# currgenTPA.net
KiCad netlist of a schematic drawn in Altium Designer
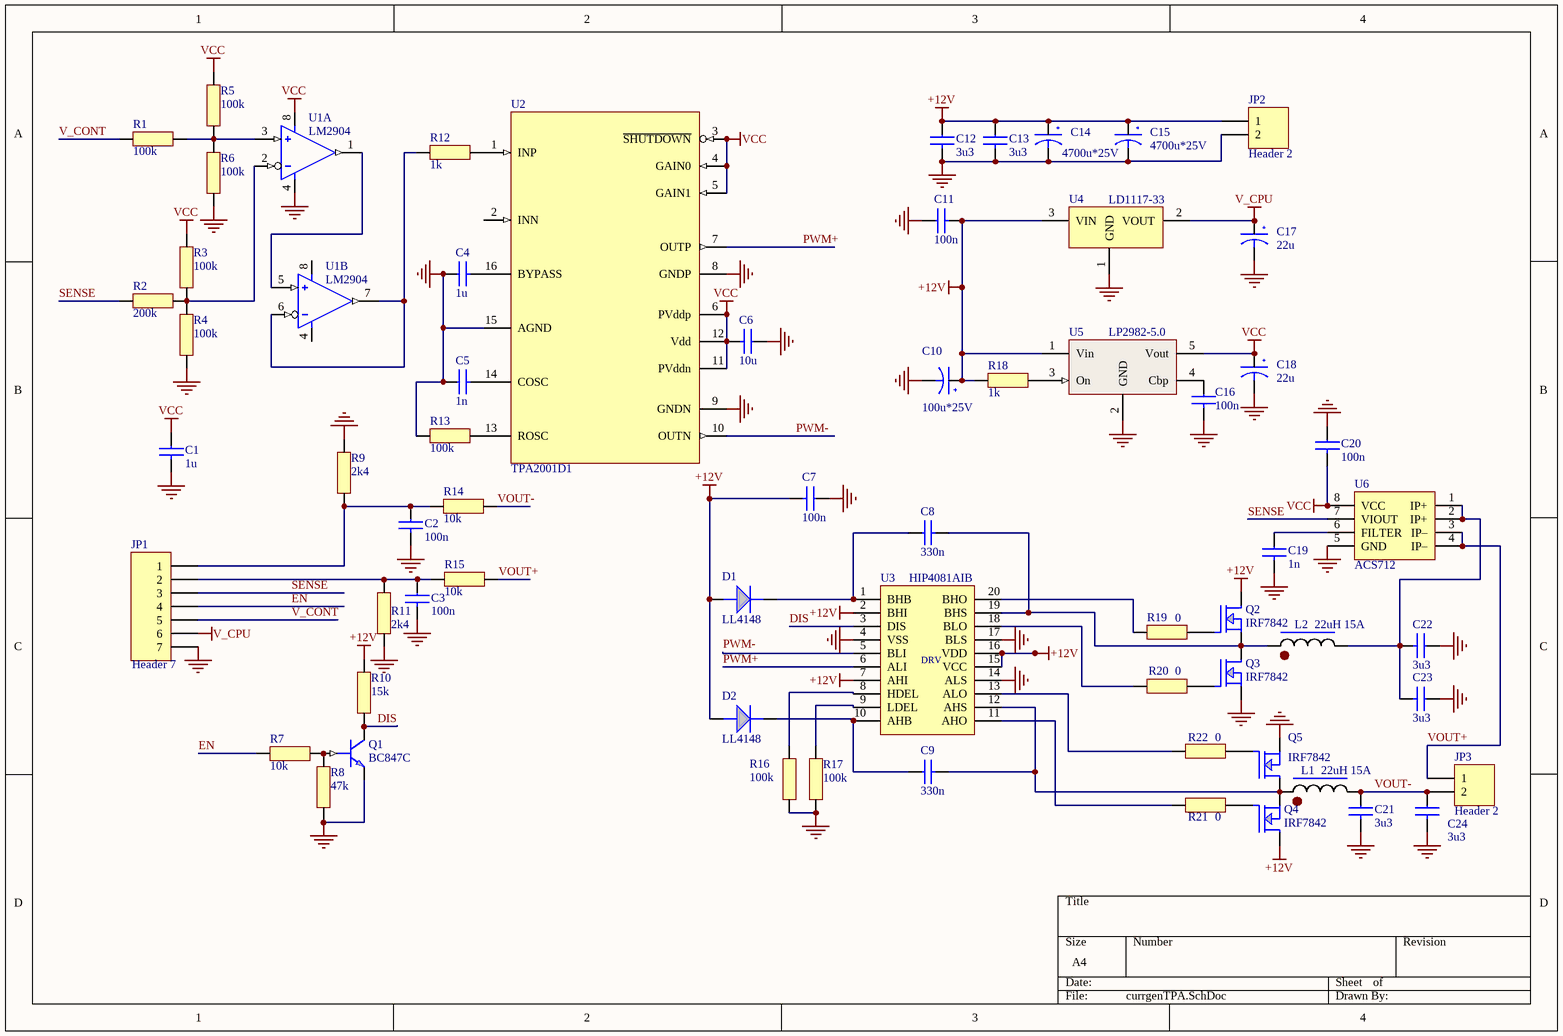
[diagram p0: currgenTPA.SchDoc]

(export (version "E")
  (design (tool "Eeschema 10.0.6"))
  (components
    (comp (ref "C1") (value "1u") (footprint "C-0805") (libsource (lib "RCS-Discret") (part "C")))
    (comp (ref "C2") (value "100n") (footprint "C-0805") (libsource (lib "RCS-Discret") (part "C")))
    (comp (ref "C3") (value "100n") (footprint "C-0805") (libsource (lib "RCS-Discret") (part "C")))
    (comp (ref "C4") (value "1u") (footprint "C-0805") (libsource (lib "RCS-Discret") (part "C")))
    (comp (ref "C5") (value "1n") (footprint "C-0805") (libsource (lib "RCS-Discret") (part "C")))
    (comp (ref "C6") (value "10u") (footprint "C-0805") (libsource (lib "RCS-Discret") (part "C")))
    (comp (ref "C7") (value "100n") (footprint "C-0805") (libsource (lib "RCS-Discret") (part "C")))
    (comp (ref "C8") (value "330n") (footprint "C-0805") (libsource (lib "RCS-Discret") (part "C")))
    (comp (ref "C9") (value "330n") (footprint "C-0805") (libsource (lib "RCS-Discret") (part "C")))
    (comp (ref "C10")
      (value "100u*25V")
      (footprint "EXR-6.3X11")
      (libsource (lib "RCS-Discret") (part "C-EL-DIP"))
    )
    (comp (ref "C11") (value "100n") (footprint "C-0805") (libsource (lib "RCS-Discret") (part "C")))
    (comp (ref "C12") (value "3u3") (footprint "C-1206") (libsource (lib "RCS-Discret") (part "C")))
    (comp (ref "C13") (value "3u3") (footprint "C-1206") (libsource (lib "RCS-Discret") (part "C")))
    (comp (ref "C14")
      (value "4700u*25V")
      (footprint "EXR-10X12.5")
      (libsource (lib "RCS-Discret") (part "C-EL-DIP"))
    )
    (comp (ref "C15")
      (value "4700u*25V")
      (footprint "EXR-10X12.5")
      (libsource (lib "RCS-Discret") (part "C-EL-DIP"))
    )
    (comp (ref "C16") (value "100n") (footprint "C-0805") (libsource (lib "RCS-Discret") (part "C")))
    (comp (ref "C17") (value "22u") (footprint "TANTAL-A") (libsource (lib "RCS-Discret") (part "C-EL-TAN")))
    (comp (ref "C18") (value "22u") (footprint "TANTAL-A") (libsource (lib "RCS-Discret") (part "C-EL-TAN")))
    (comp (ref "C19") (value "1n") (footprint "C-0805") (libsource (lib "RCS-Discret") (part "C")))
    (comp (ref "C20") (value "100n") (footprint "C-0805") (libsource (lib "RCS-Discret") (part "C")))
    (comp (ref "C21") (value "3u3") (footprint "C-1206") (libsource (lib "RCS-Discret") (part "C")))
    (comp (ref "C22") (value "3u3") (footprint "C-1206") (libsource (lib "RCS-Discret") (part "C")))
    (comp (ref "C23") (value "3u3") (footprint "C-1206") (libsource (lib "RCS-Discret") (part "C")))
    (comp (ref "C24") (value "3u3") (footprint "C-1206") (libsource (lib "RCS-Discret") (part "C")))
    (comp (ref "D1") (value "LL4148") (footprint "SOD-80") (libsource (lib "RCS-Discret") (part "DIODE")))
    (comp (ref "D2") (value "LL4148") (footprint "SOD-80") (libsource (lib "RCS-Discret") (part "DIODE")))
    (comp (ref "JP1")
      (value "Header 7")
      (footprint "HDR1X7")
      (description "Header, 7-Pin")
      (fields (field (name "PUBLISHER") "Altium Limited"))
      (libsource (lib "Miscellaneous Connectors") (part "Header 7"))
    )
    (comp (ref "JP2")
      (value "Header 2")
      (footprint "KLEMMA2")
      (description "Header, 2-Pin")
      (fields (field (name "PUBLISHER") "Altium Limited"))
      (libsource (lib "Miscellaneous Connectors") (part "Header 2"))
    )
    (comp (ref "JP3")
      (value "Header 2")
      (footprint "KLEMMA2")
      (description "Header, 2-Pin")
      (fields (field (name "PUBLISHER") "Altium Limited"))
      (libsource (lib "Miscellaneous Connectors") (part "Header 2"))
    )
    (comp (ref "L1") (value "22uH 15A") (footprint "L_TOR") (libsource (lib "RCS-Discret") (part "L*")))
    (comp (ref "L2") (value "22uH 15A") (footprint "L_TOR") (libsource (lib "RCS-Discret") (part "L*")))
    (comp (ref "Q1") (value "BC847C") (footprint "SOT-23") (libsource (lib "RCS-Discret") (part "NPN")))
    (comp (ref "Q2") (value "IRF7842") (footprint "SO8_MOSFET") (libsource (lib "currgen") (part "IRF7842")))
    (comp (ref "Q3") (value "IRF7842") (footprint "SO8_MOSFET") (libsource (lib "currgen") (part "IRF7842")))
    (comp (ref "Q4") (value "IRF7842") (footprint "SO8_MOSFET") (libsource (lib "currgen") (part "IRF7842")))
    (comp (ref "Q5") (value "IRF7842") (footprint "SO8_MOSFET") (libsource (lib "currgen") (part "IRF7842")))
    (comp (ref "R1") (value "100k") (footprint "R-0805") (libsource (lib "") (part "R_1")))
    (comp (ref "R2") (value "200k") (footprint "R-0805") (libsource (lib "") (part "R_1")))
    (comp (ref "R3") (value "100k") (footprint "R-0805") (libsource (lib "RCS-Discret") (part "R")))
    (comp (ref "R4") (value "100k") (footprint "R-0805") (libsource (lib "RCS-Discret") (part "R")))
    (comp (ref "R5") (value "100k") (footprint "R-0805") (libsource (lib "RCS-Discret") (part "R")))
    (comp (ref "R6") (value "100k") (footprint "R-0805") (libsource (lib "RCS-Discret") (part "R")))
    (comp (ref "R7") (value "10k") (footprint "R-0805") (libsource (lib "") (part "R_1")))
    (comp (ref "R8") (value "47k") (footprint "R-0805") (libsource (lib "RCS-Discret") (part "R")))
    (comp (ref "R9") (value "2k4") (footprint "R-0805") (libsource (lib "RCS-Discret") (part "R")))
    (comp (ref "R10") (value "15k") (footprint "R-0805") (libsource (lib "RCS-Discret") (part "R")))
    (comp (ref "R11") (value "2k4") (footprint "R-0805") (libsource (lib "RCS-Discret") (part "R")))
    (comp (ref "R12") (value "1k") (footprint "R-0805") (libsource (lib "") (part "R_1")))
    (comp (ref "R13") (value "100k") (footprint "R-0805") (libsource (lib "") (part "R_2")))
    (comp (ref "R14") (value "10k") (footprint "R-0805") (libsource (lib "") (part "R_1")))
    (comp (ref "R15") (value "10k") (footprint "R-0805") (libsource (lib "") (part "R_1")))
    (comp (ref "R16") (value "100k") (footprint "R-0805") (libsource (lib "") (part "R_3")))
    (comp (ref "R17") (value "100k") (footprint "R-0805") (libsource (lib "") (part "R_3")))
    (comp (ref "R18") (value "1k") (footprint "R-0805") (libsource (lib "") (part "R_1")))
    (comp (ref "R19") (value "0") (footprint "R-0805") (libsource (lib "") (part "R_1")))
    (comp (ref "R20") (value "0") (footprint "R-0805") (libsource (lib "") (part "R_1")))
    (comp (ref "R21") (value "0") (footprint "R-0805") (libsource (lib "") (part "R_1")))
    (comp (ref "R22") (value "0") (footprint "R-0805") (libsource (lib "") (part "R_1")))
    (comp (ref "U1")
      (value "LM2904")
      (footprint "SO8-(SOT-96-1)")
      (description "2 Operation amplifier")
      (libsource (lib "RCS-IMS") (part "LM2904"))
    )
    (comp (ref "U2")
      (value "TPA2001D1")
      (footprint "TSSOP16-(SOT-403-1)")
      (description "1-W FILTERLESS MONO AUDIO POWER AMPLIFIER")
      (libsource (lib "RCS-IMS") (part "TPA2001D1"))
    )
    (comp (ref "U3")
      (value "HIP4081AIB")
      (footprint "SO20-(SOT-163-1)")
      (libsource (lib "RCS-IMS") (part "HIP4081AIB"))
    )
    (comp (ref "U4")
      (value "LD1117-33")
      (footprint "SOT-223-(SC-73)")
      (libsource (lib "RCS-IMS") (part "LD1117"))
    )
    (comp (ref "U5")
      (value "LP2982-5.0")
      (footprint "SOT-23-5")
      (description "50mA Ultra Low-Dropout Regulator")
      (libsource (lib "RCS-IMS") (part "LP2982"))
    )
    (comp (ref "U6")
      (value "ACS712")
      (footprint "SO8-(SOT-96-1)")
      (libsource (lib "RCS-IMS") (part "ACS712"))
    )
  )
  (nets
    (net (code "1") (name "+12V") (class "Default")
      (node (ref "C10") (pin "2") (pinfunction "+_2") (pintype "passive"))
      (node (ref "C11") (pin "2") (pinfunction "2_2") (pintype "passive"))
      (node (ref "C12") (pin "1") (pinfunction "1_1") (pintype "passive"))
      (node (ref "C13") (pin "1") (pinfunction "1_1") (pintype "passive"))
      (node (ref "C14") (pin "2") (pinfunction "+_2") (pintype "passive"))
      (node (ref "C15") (pin "2") (pinfunction "+_2") (pintype "passive"))
      (node (ref "C7") (pin "2") (pinfunction "2_2") (pintype "passive"))
      (node (ref "D1") (pin "A") (pinfunction "A_A") (pintype "passive"))
      (node (ref "D2") (pin "A") (pinfunction "A_A") (pintype "passive"))
      (node (ref "JP2") (pin "1") (pinfunction "1_1") (pintype "passive"))
      (node (ref "Q2") (pin "5") (pinfunction "DRAIN_5") (pintype "passive"))
      (node (ref "Q4") (pin "5") (pinfunction "DRAIN_5") (pintype "passive"))
      (node (ref "R10") (pin "1") (pinfunction "1_1") (pintype "passive"))
      (node (ref "R18") (pin "1") (pinfunction "1_1") (pintype "passive"))
      (node (ref "U3") (pin "15") (pinfunction "VCC_15") (pintype "passive"))
      (node (ref "U3") (pin "16") (pinfunction "VDD_16") (pintype "passive"))
      (node (ref "U3") (pin "2") (pinfunction "BHI_2") (pintype "passive"))
      (node (ref "U3") (pin "7") (pinfunction "AHI_7") (pintype "passive"))
      (node (ref "U4") (pin "3") (pinfunction "VIN_3") (pintype "passive"))
      (node (ref "U5") (pin "1") (pinfunction "Vin_1") (pintype "power_in"))
    )
    (net (code "2") (name "/DIS") (class "Default")
      (node (ref "Q1") (pin "3") (pinfunction "COLLECTOR_3") (pintype "passive"))
      (node (ref "R10") (pin "2") (pinfunction "2_2") (pintype "passive"))
      (node (ref "U3") (pin "3") (pinfunction "DIS_3") (pintype "passive"))
    )
    (net (code "3") (name "/EN") (class "Default")
      (node (ref "JP1") (pin "4") (pinfunction "4_4") (pintype "passive"))
      (node (ref "R7") (pin "1") (pinfunction "1_1") (pintype "passive"))
    )
    (net (code "4") (name "/PWM+") (class "Default")
      (node (ref "U2") (pin "7") (pinfunction "OUTP_7") (pintype "output"))
      (node (ref "U3") (pin "6") (pinfunction "ALI_6") (pintype "passive"))
    )
    (net (code "5") (name "/PWM-") (class "Default")
      (node (ref "U2") (pin "10") (pinfunction "OUTN_10") (pintype "output"))
      (node (ref "U3") (pin "5") (pinfunction "BLI_5") (pintype "passive"))
    )
    (net (code "6") (name "/SENSE") (class "Default")
      (node (ref "JP1") (pin "3") (pinfunction "3_3") (pintype "passive"))
      (node (ref "R2") (pin "1") (pinfunction "1_1") (pintype "passive"))
      (node (ref "U6") (pin "7") (pinfunction "VIOUT_7") (pintype "passive"))
    )
    (net (code "7") (name "/VOUT+") (class "Default")
      (node (ref "JP3") (pin "1") (pinfunction "1_1") (pintype "passive"))
      (node (ref "R15") (pin "2") (pinfunction "2_2") (pintype "passive"))
      (node (ref "U6") (pin "3") (pinfunction "IP–_3") (pintype "passive"))
      (node (ref "U6") (pin "4") (pinfunction "IP–_4") (pintype "passive"))
    )
    (net (code "8") (name "/VOUT-") (class "Default")
      (node (ref "C21") (pin "1") (pinfunction "1_1") (pintype "passive"))
      (node (ref "C24") (pin "1") (pinfunction "1_1") (pintype "passive"))
      (node (ref "JP3") (pin "2") (pinfunction "2_2") (pintype "passive"))
      (node (ref "L1") (pin "2") (pinfunction "2_2") (pintype "passive"))
      (node (ref "R14") (pin "2") (pinfunction "2_2") (pintype "passive"))
    )
    (net (code "9") (name "/V_CONT") (class "Default")
      (node (ref "JP1") (pin "5") (pinfunction "5_5") (pintype "passive"))
      (node (ref "R1") (pin "1") (pinfunction "1_1") (pintype "passive"))
    )
    (net (code "10") (name "2") (class "Default")
      (node (ref "U4") (pin "4") (pinfunction "VOUT_4") (pintype "passive"))
    )
    (net (code "11") (name "GND") (class "Default")
      (node (ref "C1") (pin "2") (pinfunction "2_2") (pintype "passive"))
      (node (ref "C10") (pin "1") (pinfunction "-_1") (pintype "passive"))
      (node (ref "C11") (pin "1") (pinfunction "1_1") (pintype "passive"))
      (node (ref "C12") (pin "2") (pinfunction "2_2") (pintype "passive"))
      (node (ref "C13") (pin "2") (pinfunction "2_2") (pintype "passive"))
      (node (ref "C14") (pin "1") (pinfunction "-_1") (pintype "passive"))
      (node (ref "C15") (pin "1") (pinfunction "-_1") (pintype "passive"))
      (node (ref "C16") (pin "2") (pinfunction "2_2") (pintype "passive"))
      (node (ref "C17") (pin "1") (pinfunction "-_1") (pintype "passive"))
      (node (ref "C18") (pin "1") (pinfunction "-_1") (pintype "passive"))
      (node (ref "C19") (pin "2") (pinfunction "2_2") (pintype "passive"))
      (node (ref "C2") (pin "2") (pinfunction "2_2") (pintype "passive"))
      (node (ref "C20") (pin "1") (pinfunction "1_1") (pintype "passive"))
      (node (ref "C21") (pin "2") (pinfunction "2_2") (pintype "passive"))
      (node (ref "C22") (pin "1") (pinfunction "1_1") (pintype "passive"))
      (node (ref "C23") (pin "1") (pinfunction "1_1") (pintype "passive"))
      (node (ref "C24") (pin "2") (pinfunction "2_2") (pintype "passive"))
      (node (ref "C3") (pin "2") (pinfunction "2_2") (pintype "passive"))
      (node (ref "C4") (pin "1") (pinfunction "1_1") (pintype "passive"))
      (node (ref "C5") (pin "1") (pinfunction "1_1") (pintype "passive"))
      (node (ref "C6") (pin "1") (pinfunction "1_1") (pintype "passive"))
      (node (ref "C7") (pin "1") (pinfunction "1_1") (pintype "passive"))
      (node (ref "JP1") (pin "7") (pinfunction "7_7") (pintype "passive"))
      (node (ref "JP2") (pin "2") (pinfunction "2_2") (pintype "passive"))
      (node (ref "Q1") (pin "1") (pinfunction "EMITTER_1") (pintype "passive"))
      (node (ref "Q3") (pin "1") (pinfunction "SOURCE_1") (pintype "passive"))
      (node (ref "Q5") (pin "1") (pinfunction "SOURCE_1") (pintype "passive"))
      (node (ref "R11") (pin "2") (pinfunction "2_2") (pintype "passive"))
      (node (ref "R13") (pin "2") (pinfunction "2_2") (pintype "passive"))
      (node (ref "R16") (pin "1") (pinfunction "1_1") (pintype "passive"))
      (node (ref "R17") (pin "1") (pinfunction "1_1") (pintype "passive"))
      (node (ref "R4") (pin "2") (pinfunction "2_2") (pintype "passive"))
      (node (ref "R6") (pin "2") (pinfunction "2_2") (pintype "passive"))
      (node (ref "R8") (pin "2") (pinfunction "2_2") (pintype "passive"))
      (node (ref "R9") (pin "1") (pinfunction "1_1") (pintype "passive"))
      (node (ref "U1") (pin "4") (pinfunction "V-_4") (pintype "power_in"))
      (node (ref "U2") (pin "15") (pinfunction "AGND_15") (pintype "passive"))
      (node (ref "U2") (pin "8") (pinfunction "GNDP_8") (pintype "power_in"))
      (node (ref "U2") (pin "9") (pinfunction "GNDN_9") (pintype "power_in"))
      (node (ref "U3") (pin "14") (pinfunction "ALS_14") (pintype "passive"))
      (node (ref "U3") (pin "17") (pinfunction "BLS_17") (pintype "passive"))
      (node (ref "U3") (pin "4") (pinfunction "VSS_4") (pintype "passive"))
      (node (ref "U4") (pin "1") (pinfunction "GND_1") (pintype "passive"))
      (node (ref "U5") (pin "2") (pinfunction "GND_2") (pintype "power_in"))
      (node (ref "U6") (pin "5") (pinfunction "GND_5") (pintype "passive"))
    )
    (net (code "12") (name "Net-(C2-Pad1)") (class "Default")
      (node (ref "C2") (pin "1") (pinfunction "1_1") (pintype "passive"))
      (node (ref "JP1") (pin "1") (pinfunction "1_1") (pintype "passive"))
      (node (ref "R14") (pin "1") (pinfunction "1_1") (pintype "passive"))
      (node (ref "R9") (pin "2") (pinfunction "2_2") (pintype "passive"))
    )
    (net (code "13") (name "Net-(C3-Pad1)") (class "Default")
      (node (ref "C3") (pin "1") (pinfunction "1_1") (pintype "passive"))
      (node (ref "JP1") (pin "2") (pinfunction "2_2") (pintype "passive"))
      (node (ref "R11") (pin "1") (pinfunction "1_1") (pintype "passive"))
      (node (ref "R15") (pin "1") (pinfunction "1_1") (pintype "passive"))
    )
    (net (code "14") (name "Net-(C22-Pad2)") (class "Default")
      (node (ref "C22") (pin "2") (pinfunction "2_2") (pintype "passive"))
      (node (ref "C23") (pin "2") (pinfunction "2_2") (pintype "passive"))
      (node (ref "L2") (pin "2") (pinfunction "2_2") (pintype "passive"))
      (node (ref "U6") (pin "1") (pinfunction "IP+_1") (pintype "passive"))
      (node (ref "U6") (pin "2") (pinfunction "IP+_2") (pintype "passive"))
    )
    (net (code "15") (name "Net-(Q1-BASE)") (class "Default")
      (node (ref "Q1") (pin "2") (pinfunction "BASE_2") (pintype "input"))
      (node (ref "R7") (pin "2") (pinfunction "2_2") (pintype "passive"))
      (node (ref "R8") (pin "1") (pinfunction "1_1") (pintype "passive"))
    )
    (net (code "16") (name "Net-(Q2-GATE)") (class "Default")
      (node (ref "Q2") (pin "4") (pinfunction "GATE_4") (pintype "passive"))
      (node (ref "R19") (pin "2") (pinfunction "2_2") (pintype "passive"))
    )
    (net (code "17") (name "Net-(Q2-SOURCE)") (class "Default")
      (node (ref "C8") (pin "2") (pinfunction "2_2") (pintype "passive"))
      (node (ref "L2") (pin "1") (pinfunction "1_1") (pintype "passive"))
      (node (ref "Q2") (pin "1") (pinfunction "SOURCE_1") (pintype "passive"))
      (node (ref "Q3") (pin "5") (pinfunction "DRAIN_5") (pintype "passive"))
      (node (ref "U3") (pin "19") (pinfunction "BHS_19") (pintype "passive"))
    )
    (net (code "18") (name "Net-(Q3-GATE)") (class "Default")
      (node (ref "Q3") (pin "4") (pinfunction "GATE_4") (pintype "passive"))
      (node (ref "R20") (pin "2") (pinfunction "2_2") (pintype "passive"))
    )
    (net (code "19") (name "Net-(Q4-GATE)") (class "Default")
      (node (ref "Q4") (pin "4") (pinfunction "GATE_4") (pintype "passive"))
      (node (ref "R21") (pin "2") (pinfunction "2_2") (pintype "passive"))
    )
    (net (code "20") (name "Net-(Q4-SOURCE)") (class "Default")
      (node (ref "C9") (pin "2") (pinfunction "2_2") (pintype "passive"))
      (node (ref "L1") (pin "1") (pinfunction "1_1") (pintype "passive"))
      (node (ref "Q4") (pin "1") (pinfunction "SOURCE_1") (pintype "passive"))
      (node (ref "Q5") (pin "5") (pinfunction "DRAIN_5") (pintype "passive"))
      (node (ref "U3") (pin "12") (pinfunction "AHS_12") (pintype "passive"))
    )
    (net (code "21") (name "Net-(Q5-GATE)") (class "Default")
      (node (ref "Q5") (pin "4") (pinfunction "GATE_4") (pintype "passive"))
      (node (ref "R22") (pin "2") (pinfunction "2_2") (pintype "passive"))
    )
    (net (code "22") (name "Net-(U1A-+IN)") (class "Default")
      (node (ref "R1") (pin "2") (pinfunction "2_2") (pintype "passive"))
      (node (ref "R5") (pin "2") (pinfunction "2_2") (pintype "passive"))
      (node (ref "R6") (pin "1") (pinfunction "1_1") (pintype "passive"))
      (node (ref "U1") (pin "3") (pinfunction "+IN_3") (pintype "input"))
    )
    (net (code "23") (name "Net-(U1A--IN)") (class "Default")
      (node (ref "R2") (pin "2") (pinfunction "2_2") (pintype "passive"))
      (node (ref "R3") (pin "2") (pinfunction "2_2") (pintype "passive"))
      (node (ref "R4") (pin "1") (pinfunction "1_1") (pintype "passive"))
      (node (ref "U1") (pin "2") (pinfunction "-IN_2") (pintype "input"))
    )
    (net (code "24") (name "Net-(U1A-OUT)") (class "Default")
      (node (ref "U1") (pin "1") (pinfunction "OUT_1") (pintype "output"))
      (node (ref "U1") (pin "5") (pinfunction "+IN_5") (pintype "input"))
    )
    (net (code "25") (name "Net-(U1B--IN)") (class "Default")
      (node (ref "R12") (pin "1") (pinfunction "1_1") (pintype "passive"))
      (node (ref "U1") (pin "6") (pinfunction "-IN_6") (pintype "input"))
      (node (ref "U1") (pin "7") (pinfunction "OUT_7") (pintype "output"))
    )
    (net (code "26") (name "Net-(U2-BYPASS)") (class "Default")
      (node (ref "C4") (pin "2") (pinfunction "2_2") (pintype "passive"))
      (node (ref "U2") (pin "16") (pinfunction "BYPASS_16") (pintype "passive"))
    )
    (net (code "27") (name "Net-(U2-COSC)") (class "Default")
      (node (ref "C5") (pin "2") (pinfunction "2_2") (pintype "passive"))
      (node (ref "U2") (pin "14") (pinfunction "COSC_14") (pintype "passive"))
    )
    (net (code "28") (name "Net-(U2-INP)") (class "Default")
      (node (ref "R12") (pin "2") (pinfunction "2_2") (pintype "passive"))
      (node (ref "U2") (pin "1") (pinfunction "INP_1") (pintype "input"))
    )
    (net (code "29") (name "Net-(U2-ROSC)") (class "Default")
      (node (ref "R13") (pin "1") (pinfunction "1_1") (pintype "passive"))
      (node (ref "U2") (pin "13") (pinfunction "ROSC_13") (pintype "passive"))
    )
    (net (code "30") (name "Net-(U3-AHB)") (class "Default")
      (node (ref "C9") (pin "1") (pinfunction "1_1") (pintype "passive"))
      (node (ref "D2") (pin "K") (pinfunction "K_K") (pintype "passive"))
      (node (ref "U3") (pin "10") (pinfunction "AHB_10") (pintype "passive"))
    )
    (net (code "31") (name "Net-(U3-AHO)") (class "Default")
      (node (ref "R21") (pin "1") (pinfunction "1_1") (pintype "passive"))
      (node (ref "U3") (pin "11") (pinfunction "AHO_11") (pintype "passive"))
    )
    (net (code "32") (name "Net-(U3-ALO)") (class "Default")
      (node (ref "R22") (pin "1") (pinfunction "1_1") (pintype "passive"))
      (node (ref "U3") (pin "13") (pinfunction "ALO_13") (pintype "passive"))
    )
    (net (code "33") (name "Net-(U3-BHB)") (class "Default")
      (node (ref "C8") (pin "1") (pinfunction "1_1") (pintype "passive"))
      (node (ref "D1") (pin "K") (pinfunction "K_K") (pintype "passive"))
      (node (ref "U3") (pin "1") (pinfunction "BHB_1") (pintype "passive"))
    )
    (net (code "34") (name "Net-(U3-BHO)") (class "Default")
      (node (ref "R19") (pin "1") (pinfunction "1_1") (pintype "passive"))
      (node (ref "U3") (pin "20") (pinfunction "BHO_20") (pintype "passive"))
    )
    (net (code "35") (name "Net-(U3-BLO)") (class "Default")
      (node (ref "R20") (pin "1") (pinfunction "1_1") (pintype "passive"))
      (node (ref "U3") (pin "18") (pinfunction "BLO_18") (pintype "passive"))
    )
    (net (code "36") (name "Net-(U3-HDEL)") (class "Default")
      (node (ref "R16") (pin "2") (pinfunction "2_2") (pintype "passive"))
      (node (ref "U3") (pin "8") (pinfunction "HDEL_8") (pintype "passive"))
    )
    (net (code "37") (name "Net-(U3-LDEL)") (class "Default")
      (node (ref "R17") (pin "2") (pinfunction "2_2") (pintype "passive"))
      (node (ref "U3") (pin "9") (pinfunction "LDEL_9") (pintype "passive"))
    )
    (net (code "38") (name "Net-(U5-Cbp)") (class "Default")
      (node (ref "C16") (pin "1") (pinfunction "1_1") (pintype "passive"))
      (node (ref "U5") (pin "4") (pinfunction "Cbp_4") (pintype "passive"))
    )
    (net (code "39") (name "Net-(U5-On)") (class "Default")
      (node (ref "R18") (pin "2") (pinfunction "2_2") (pintype "passive"))
      (node (ref "U5") (pin "3") (pinfunction "On_3") (pintype "input"))
    )
    (net (code "40") (name "Net-(U6-FILTER)") (class "Default")
      (node (ref "C19") (pin "1") (pinfunction "1_1") (pintype "passive"))
      (node (ref "U6") (pin "6") (pinfunction "FILTER_6") (pintype "passive"))
    )
    (net (code "41") (name "VCC") (class "Default")
      (node (ref "C1") (pin "1") (pinfunction "1_1") (pintype "passive"))
      (node (ref "C18") (pin "2") (pinfunction "+_2") (pintype "passive"))
      (node (ref "C20") (pin "2") (pinfunction "2_2") (pintype "passive"))
      (node (ref "C6") (pin "2") (pinfunction "2_2") (pintype "passive"))
      (node (ref "R3") (pin "1") (pinfunction "1_1") (pintype "passive"))
      (node (ref "R5") (pin "1") (pinfunction "1_1") (pintype "passive"))
      (node (ref "U1") (pin "8") (pinfunction "V+_8") (pintype "power_in"))
      (node (ref "U2") (pin "11") (pinfunction "PVddn_11") (pintype "passive"))
      (node (ref "U2") (pin "12") (pinfunction "Vdd_12") (pintype "passive"))
      (node (ref "U2") (pin "3") (pinfunction "~{SHUTDOWN}_3") (pintype "input"))
      (node (ref "U2") (pin "4") (pinfunction "GAIN0_4") (pintype "input"))
      (node (ref "U2") (pin "5") (pinfunction "GAIN1_5") (pintype "input"))
      (node (ref "U2") (pin "6") (pinfunction "PVddp_6") (pintype "passive"))
      (node (ref "U5") (pin "5") (pinfunction "Vout_5") (pintype "power_in"))
      (node (ref "U6") (pin "8") (pinfunction "VCC_8") (pintype "passive"))
    )
    (net (code "42") (name "V_CPU") (class "Default")
      (node (ref "C17") (pin "2") (pinfunction "+_2") (pintype "passive"))
      (node (ref "JP1") (pin "6") (pinfunction "6_6") (pintype "passive"))
      (node (ref "U4") (pin "2") (pinfunction "VOUT_2") (pintype "passive"))
    )
    (net (code "43") (name "unconnected-(U1B-V+-Pad8)") (class "Default")
      (node (ref "U1") (pin "8") (pinfunction "V+_8") (pintype "passive"))
    )
    (net (code "44") (name "unconnected-(U1B-V--Pad4)") (class "Default")
      (node (ref "U1") (pin "4") (pinfunction "V-_4") (pintype "passive"))
    )
    (net (code "45") (name "unconnected-(U2-INN-Pad2)") (class "Default")
      (node (ref "U2") (pin "2") (pinfunction "INN_2") (pintype "input"))
    )
  )
)
